# THT.net
KiCad netlist of a schematic drawn in EAGLE
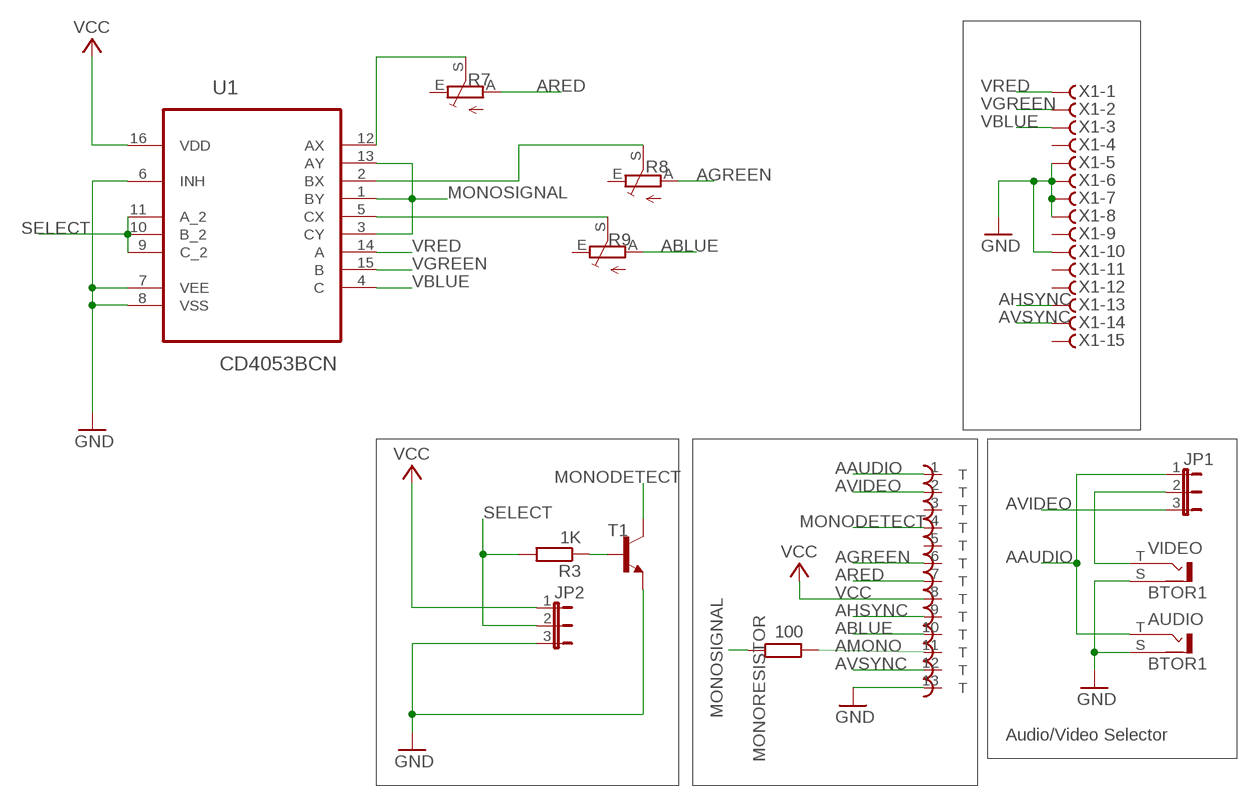
[diagram p0: schematic, sheet 1]

(export (version "E")
  (design (tool "Eeschema 10.0.6"))
  (components
    (comp (ref "ATARIOUT")
      (value "DIN13T")
      (footprint "eagle-import:ADADS")
      (libsource (lib "eagle-import") (part "DIN13T"))
    )
    (comp (ref "AUDIO")
      (value "BTOR1")
      (footprint "eagle-import:BTOR1")
      (libsource (lib "eagle-import") (part "BTOR1"))
    )
    (comp (ref "JP1")
      (value "JP2E")
      (footprint "eagle-import:JP2")
      (libsource (lib "eagle-import") (part "JP2E"))
    )
    (comp (ref "JP2")
      (value "JP2E")
      (footprint "eagle-import:JP2")
      (libsource (lib "eagle-import") (part "JP2E"))
    )
    (comp (ref "MONORESISTOR")
      (value "100")
      (footprint "eagle-import:0207_2V")
      (libsource (lib "eagle-import") (part "R-EU_0207/2V"))
    )
    (comp (ref "R3")
      (value "1K")
      (footprint "eagle-import:0207_2V")
      (libsource (lib "eagle-import") (part "R-EU_0207/2V"))
    )
    (comp (ref "R7")
      (value "TRIM_EU-CA6H")
      (footprint "eagle-import:CA6H")
      (libsource (lib "eagle-import") (part "TRIM_EU-CA6H"))
    )
    (comp (ref "R8")
      (value "TRIM_EU-CA6H")
      (footprint "eagle-import:CA6H")
      (libsource (lib "eagle-import") (part "TRIM_EU-CA6H"))
    )
    (comp (ref "R9")
      (value "TRIM_EU-CA6H")
      (footprint "eagle-import:CA6H")
      (libsource (lib "eagle-import") (part "TRIM_EU-CA6H"))
    )
    (comp (ref "T1")
      (value "2N3904-NPN-TO92-EBC")
      (footprint "eagle-import:TO92-EBC")
      (libsource (lib "eagle-import") (part "-NPN-TO92-EBC2N3904"))
    )
    (comp (ref "U1")
      (value "CD4053BCN")
      (footprint "eagle-import:DIP254P762X508-16")
      (libsource (lib "eagle-import") (part "CD4053BCN"))
    )
    (comp (ref "VIDEO")
      (value "BTOR1")
      (footprint "eagle-import:BTOR1")
      (libsource (lib "eagle-import") (part "BTOR1"))
    )
    (comp (ref "X1")
      (value "F15HDVS")
      (footprint "eagle-import:HDF15V")
      (libsource (lib "eagle-import") (part "F15?SHDV"))
    )
  )
  (nets
    (net (code "1") (name "/AAUDIO") (class "Default")
      (node (ref "ATARIOUT") (pin "1") (pinfunction "T_1") (pintype "passive"))
      (node (ref "AUDIO") (pin "T") (pinfunction "1_T") (pintype "passive"))
      (node (ref "JP1") (pin "1") (pinfunction "1_1") (pintype "passive"))
    )
    (net (code "2") (name "/ABLUE") (class "Default")
      (node (ref "ATARIOUT") (pin "10") (pinfunction "T_10") (pintype "passive"))
      (node (ref "R9") (pin "A") (pinfunction "A_A") (pintype "passive"))
    )
    (net (code "3") (name "/AGREEN") (class "Default")
      (node (ref "ATARIOUT") (pin "6") (pinfunction "T_6") (pintype "passive"))
      (node (ref "R8") (pin "A") (pinfunction "A_A") (pintype "passive"))
    )
    (net (code "4") (name "/AHSYNC") (class "Default")
      (node (ref "ATARIOUT") (pin "9") (pinfunction "T_9") (pintype "passive"))
      (node (ref "X1") (pin "13") (pinfunction "F_13") (pintype "passive"))
    )
    (net (code "5") (name "/AMONO") (class "Default")
      (node (ref "ATARIOUT") (pin "11") (pinfunction "T_11") (pintype "passive"))
      (node (ref "MONORESISTOR") (pin "2") (pinfunction "2_2") (pintype "passive"))
    )
    (net (code "6") (name "/ARED") (class "Default")
      (node (ref "ATARIOUT") (pin "7") (pinfunction "T_7") (pintype "passive"))
      (node (ref "R7") (pin "A") (pinfunction "A_A") (pintype "passive"))
    )
    (net (code "7") (name "/AVIDEO") (class "Default")
      (node (ref "ATARIOUT") (pin "2") (pinfunction "T_2") (pintype "passive"))
      (node (ref "JP1") (pin "3") (pinfunction "3_3") (pintype "passive"))
    )
    (net (code "8") (name "/AVSYNC") (class "Default")
      (node (ref "ATARIOUT") (pin "12") (pinfunction "T_12") (pintype "passive"))
      (node (ref "X1") (pin "14") (pinfunction "F_14") (pintype "passive"))
    )
    (net (code "9") (name "/MONODETECT") (class "Default")
      (node (ref "ATARIOUT") (pin "4") (pinfunction "T_4") (pintype "passive"))
      (node (ref "T1") (pin "C") (pinfunction "C_C") (pintype "passive"))
    )
    (net (code "10") (name "/MONOSIGNAL") (class "Default")
      (node (ref "MONORESISTOR") (pin "1") (pinfunction "1_1") (pintype "passive"))
      (node (ref "U1") (pin "1") (pinfunction "BY_1") (pintype "bidirectional"))
      (node (ref "U1") (pin "13") (pinfunction "AY_13") (pintype "bidirectional"))
      (node (ref "U1") (pin "3") (pinfunction "CY_3") (pintype "bidirectional"))
    )
    (net (code "11") (name "/SELECT") (class "Default")
      (node (ref "JP2") (pin "2") (pinfunction "2_2") (pintype "passive"))
      (node (ref "R3") (pin "2") (pinfunction "2_2") (pintype "passive"))
      (node (ref "U1") (pin "10") (pinfunction "B_2_10") (pintype "input"))
      (node (ref "U1") (pin "11") (pinfunction "A_2_11") (pintype "input"))
      (node (ref "U1") (pin "9") (pinfunction "C_2_9") (pintype "input"))
    )
    (net (code "12") (name "/VBLUE") (class "Default")
      (node (ref "U1") (pin "4") (pinfunction "C_4") (pintype "bidirectional"))
      (node (ref "X1") (pin "3") (pinfunction "F_3") (pintype "passive"))
    )
    (net (code "13") (name "/VGREEN") (class "Default")
      (node (ref "U1") (pin "15") (pinfunction "B_15") (pintype "bidirectional"))
      (node (ref "X1") (pin "2") (pinfunction "F_2") (pintype "passive"))
    )
    (net (code "14") (name "/VRED") (class "Default")
      (node (ref "U1") (pin "14") (pinfunction "A_14") (pintype "bidirectional"))
      (node (ref "X1") (pin "1") (pinfunction "F_1") (pintype "passive"))
    )
    (net (code "15") (name "GND") (class "Default")
      (node (ref "ATARIOUT") (pin "13") (pinfunction "T_13") (pintype "passive"))
      (node (ref "AUDIO") (pin "S") (pinfunction "2_S") (pintype "passive"))
      (node (ref "JP2") (pin "3") (pinfunction "3_3") (pintype "passive"))
      (node (ref "T1") (pin "E") (pinfunction "E_E") (pintype "passive"))
      (node (ref "U1") (pin "6") (pinfunction "INH_6") (pintype "passive"))
      (node (ref "U1") (pin "7") (pinfunction "VEE_7") (pintype "power_in"))
      (node (ref "U1") (pin "8") (pinfunction "VSS_8") (pintype "power_in"))
      (node (ref "VIDEO") (pin "S") (pinfunction "2_S") (pintype "passive"))
      (node (ref "X1") (pin "10") (pinfunction "F_10") (pintype "passive"))
      (node (ref "X1") (pin "5") (pinfunction "F_5") (pintype "passive"))
      (node (ref "X1") (pin "6") (pinfunction "F_6") (pintype "passive"))
      (node (ref "X1") (pin "7") (pinfunction "F_7") (pintype "passive"))
      (node (ref "X1") (pin "8") (pinfunction "F_8") (pintype "passive"))
    )
    (net (code "16") (name "Net-(R3-Pad1)") (class "Default")
      (node (ref "R3") (pin "1") (pinfunction "1_1") (pintype "passive"))
      (node (ref "T1") (pin "B") (pinfunction "B_B") (pintype "passive"))
    )
    (net (code "17") (name "Net-(U1-AX)") (class "Default")
      (node (ref "R7") (pin "S") (pinfunction "S_S") (pintype "passive"))
      (node (ref "U1") (pin "12") (pinfunction "AX_12") (pintype "bidirectional"))
    )
    (net (code "18") (name "Net-(U1-BX)") (class "Default")
      (node (ref "R8") (pin "S") (pinfunction "S_S") (pintype "passive"))
      (node (ref "U1") (pin "2") (pinfunction "BX_2") (pintype "bidirectional"))
    )
    (net (code "19") (name "Net-(U1-CX)") (class "Default")
      (node (ref "R9") (pin "S") (pinfunction "S_S") (pintype "passive"))
      (node (ref "U1") (pin "5") (pinfunction "CX_5") (pintype "bidirectional"))
    )
    (net (code "20") (name "Net-(VIDEO-1)") (class "Default")
      (node (ref "JP1") (pin "2") (pinfunction "2_2") (pintype "passive"))
      (node (ref "VIDEO") (pin "T") (pinfunction "1_T") (pintype "passive"))
    )
    (net (code "21") (name "VCC") (class "Default")
      (node (ref "ATARIOUT") (pin "8") (pinfunction "T_8") (pintype "passive"))
      (node (ref "JP2") (pin "1") (pinfunction "1_1") (pintype "passive"))
      (node (ref "U1") (pin "16") (pinfunction "VDD_16") (pintype "power_in"))
    )
    (net (code "22") (name "unconnected-(ATARIOUTG-T-Pad3)") (class "Default")
      (node (ref "ATARIOUT") (pin "3") (pinfunction "T_3") (pintype "passive"))
    )
    (net (code "23") (name "unconnected-(ATARIOUTI-T-Pad5)") (class "Default")
      (node (ref "ATARIOUT") (pin "5") (pinfunction "T_5") (pintype "passive"))
    )
    (net (code "24") (name "unconnected-(AUDIO-2-PadS@1)") (class "Default")
      (node (ref "AUDIO") (pin "S@1") (pinfunction "2_S@1") (pintype "passive"))
    )
    (net (code "25") (name "unconnected-(AUDIO-2-PadS@2)") (class "Default")
      (node (ref "AUDIO") (pin "S@2") (pinfunction "2_S@2") (pintype "passive"))
    )
    (net (code "26") (name "unconnected-(AUDIO-2-PadS@3)") (class "Default")
      (node (ref "AUDIO") (pin "S@3") (pinfunction "2_S@3") (pintype "passive"))
    )
    (net (code "27") (name "unconnected-(R7-PadE)") (class "Default")
      (node (ref "R7") (pin "E") (pinfunction "E_E") (pintype "passive"))
    )
    (net (code "28") (name "unconnected-(R8-PadE)") (class "Default")
      (node (ref "R8") (pin "E") (pinfunction "E_E") (pintype "passive"))
    )
    (net (code "29") (name "unconnected-(R9-PadE)") (class "Default")
      (node (ref "R9") (pin "E") (pinfunction "E_E") (pintype "passive"))
    )
    (net (code "30") (name "unconnected-(VIDEO-2-PadS@1)") (class "Default")
      (node (ref "VIDEO") (pin "S@1") (pinfunction "2_S@1") (pintype "passive"))
    )
    (net (code "31") (name "unconnected-(VIDEO-2-PadS@2)") (class "Default")
      (node (ref "VIDEO") (pin "S@2") (pinfunction "2_S@2") (pintype "passive"))
    )
    (net (code "32") (name "unconnected-(VIDEO-2-PadS@3)") (class "Default")
      (node (ref "VIDEO") (pin "S@3") (pinfunction "2_S@3") (pintype "passive"))
    )
    (net (code "33") (name "unconnected-(X1C-F-Pad11)") (class "Default")
      (node (ref "X1") (pin "11") (pinfunction "F_11") (pintype "passive"))
    )
    (net (code "34") (name "unconnected-(X1D-F-Pad12)") (class "Default")
      (node (ref "X1") (pin "12") (pinfunction "F_12") (pintype "passive"))
    )
    (net (code "35") (name "unconnected-(X1G-F-Pad15)") (class "Default")
      (node (ref "X1") (pin "15") (pinfunction "F_15") (pintype "passive"))
    )
    (net (code "36") (name "unconnected-(X1J-F-Pad4)") (class "Default")
      (node (ref "X1") (pin "4") (pinfunction "F_4") (pintype "passive"))
    )
    (net (code "37") (name "unconnected-(X1O-F-Pad9)") (class "Default")
      (node (ref "X1") (pin "9") (pinfunction "F_9") (pintype "passive"))
    )
  )
)
